# PWR_MGMT.net
KiCad netlist of a schematic drawn in Altium Designer
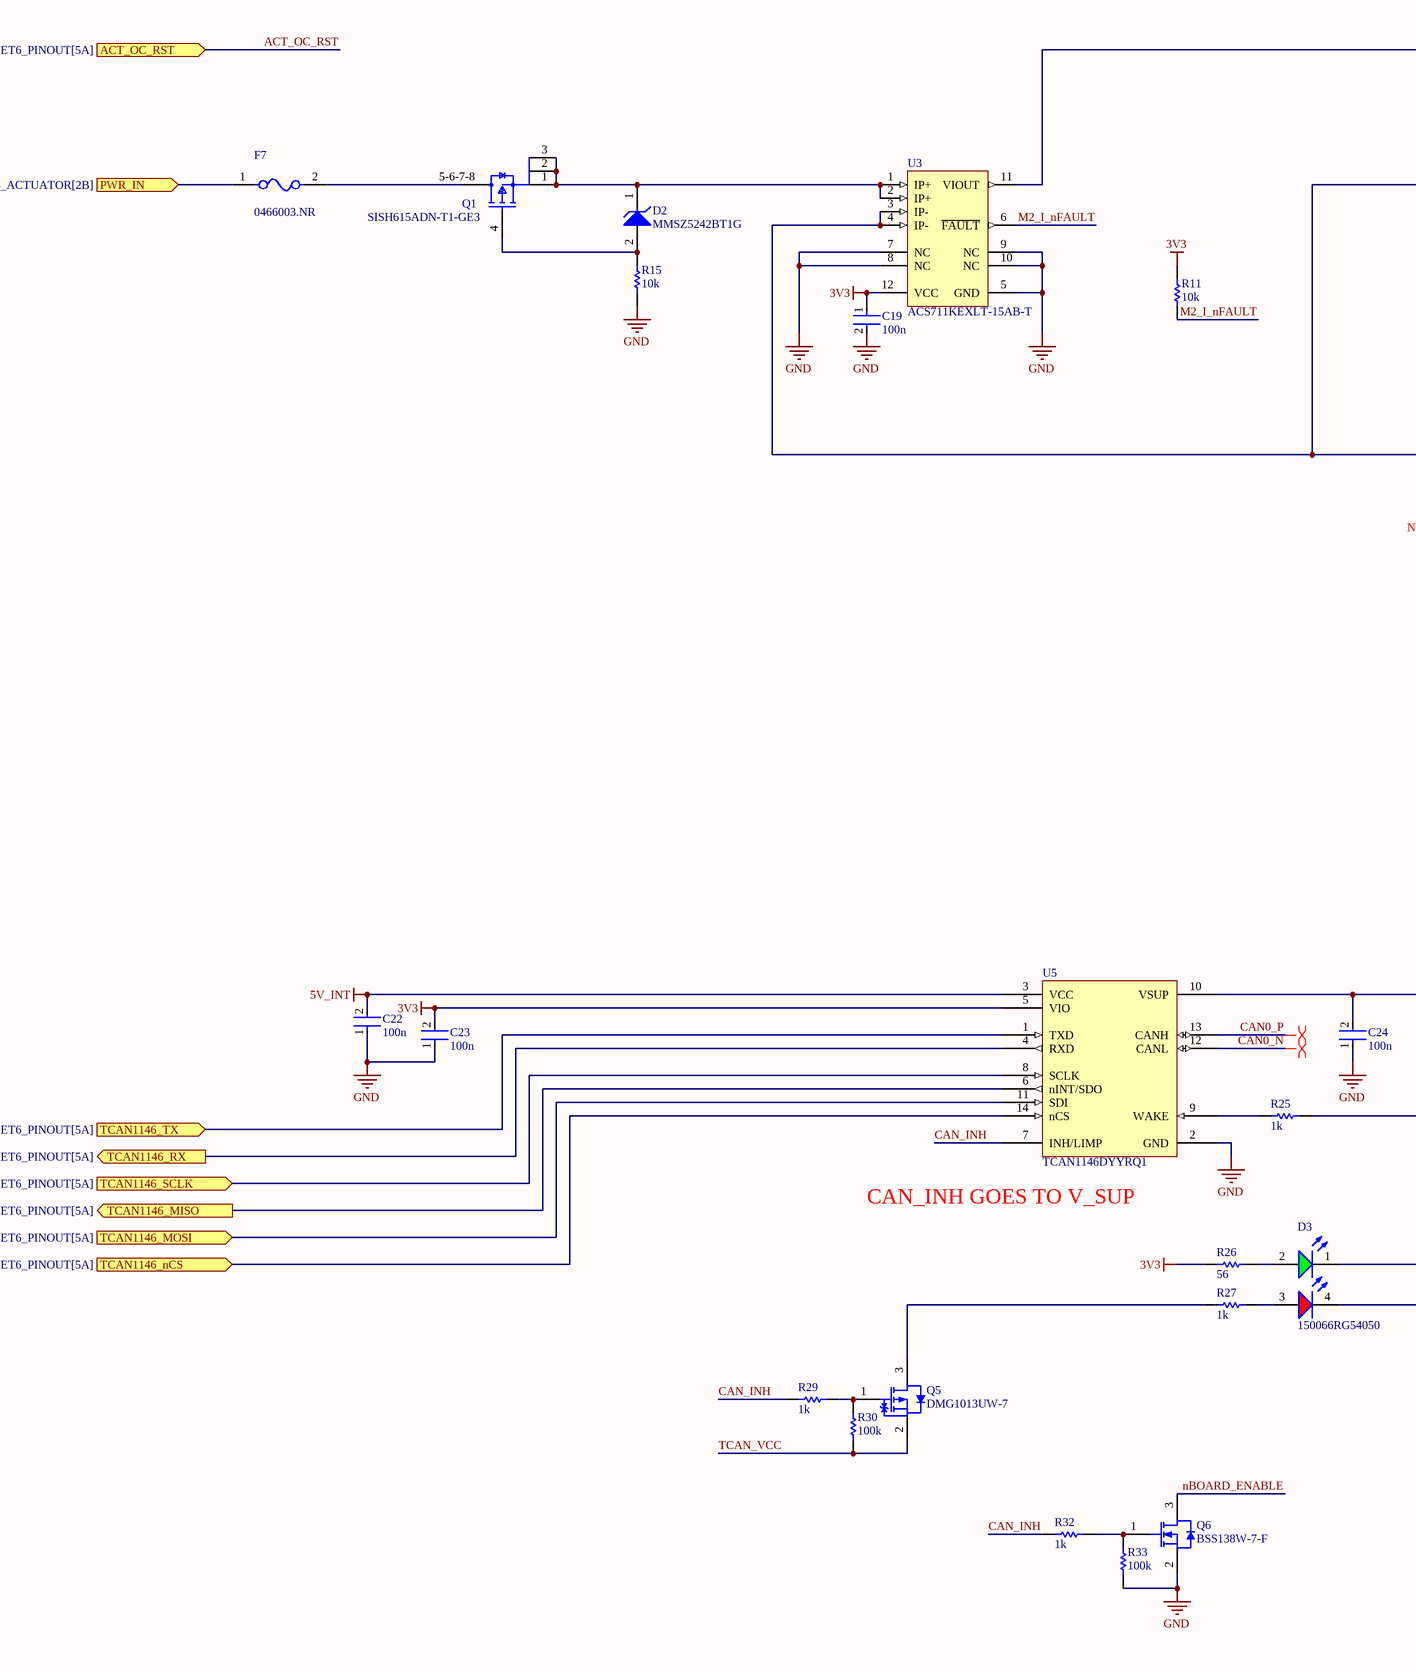
[diagram p0: PWR_MGMT.SchDoc, left]
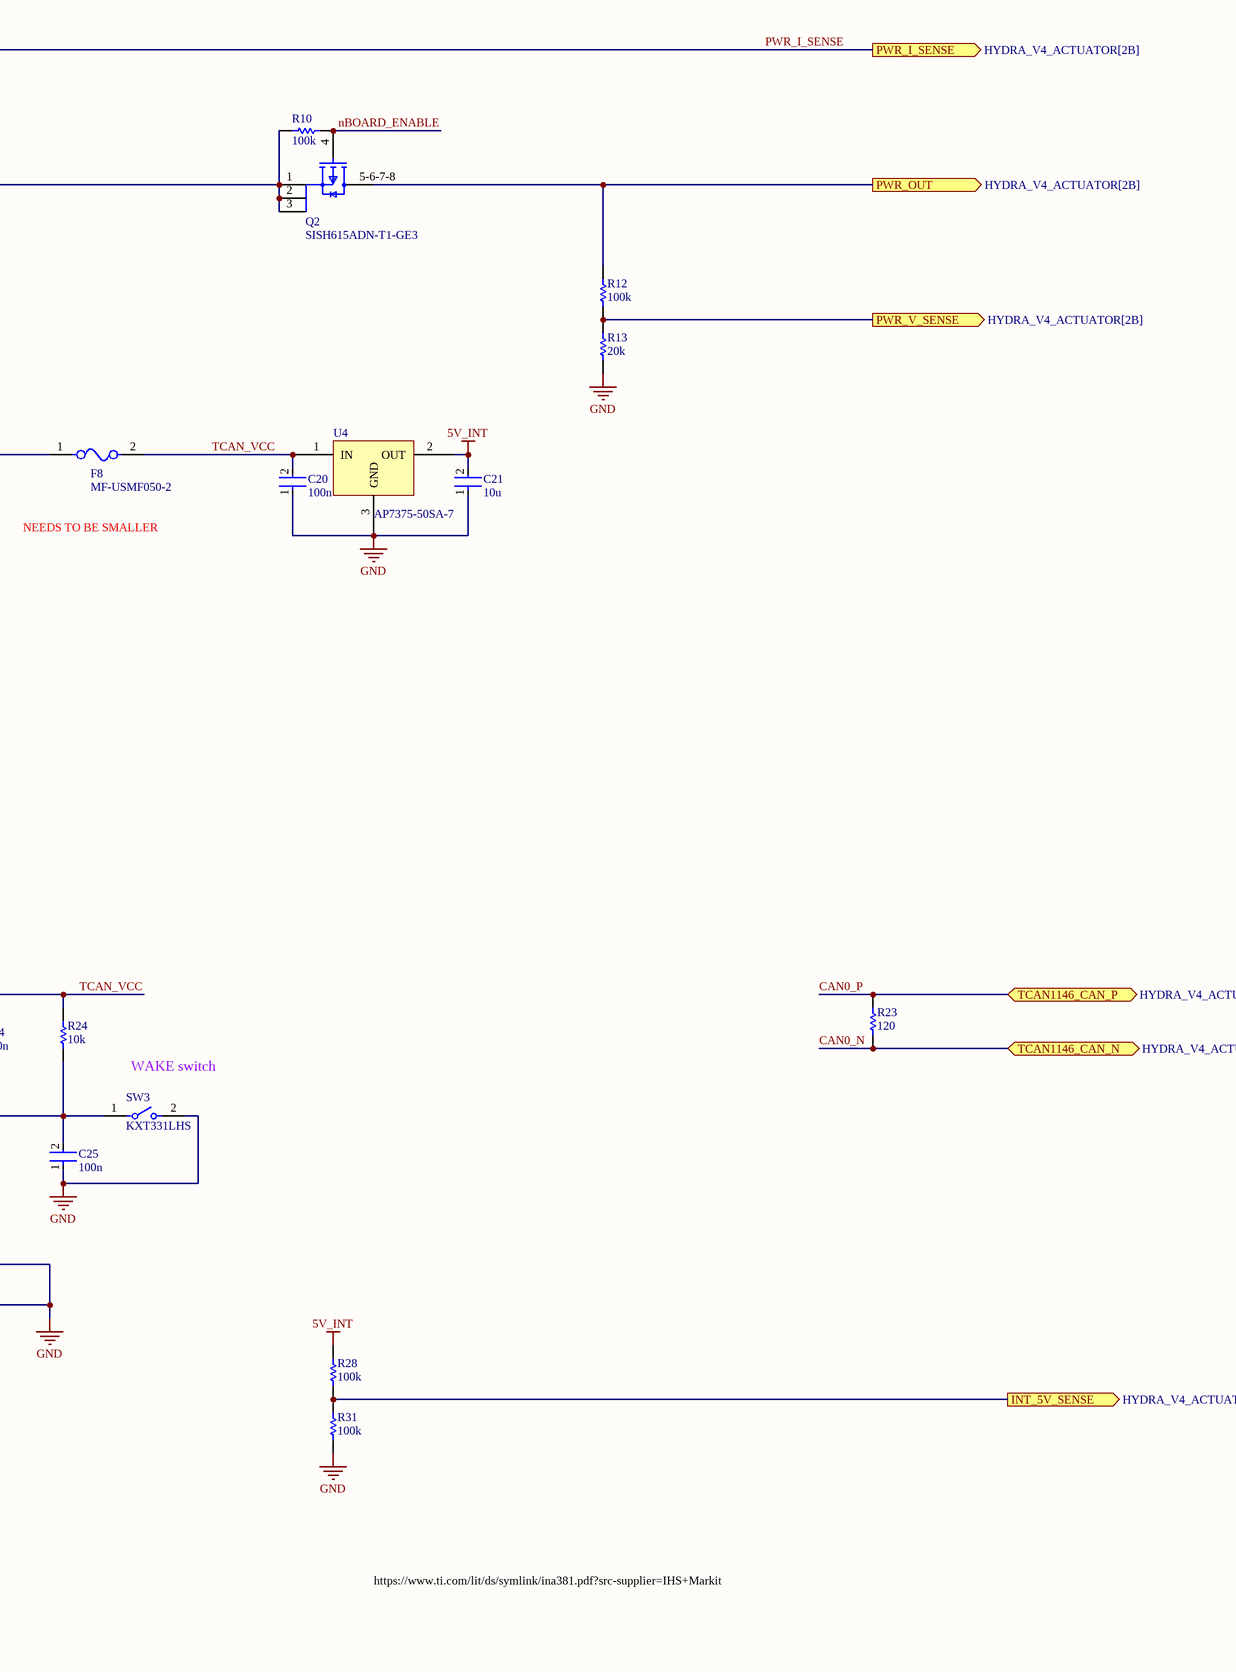
[diagram p1: PWR_MGMT.SchDoc, right]

(export (version "E")
  (design (tool "Eeschema 10.0.6"))
  (components
    (comp (ref "C19")
      (value "100n")
      (footprint "FP-0402-L_1_0_0_05-W_0_5-IPC_A")
      (description "LARGE PADS, 0402 CAP, CHANGE COMMENT TO MATCH REAL P/N")
      (libsource (lib "Space Concordia") (part "b4654b650e69147ec39a6b967a45e02"))
    )
    (comp (ref "C20")
      (value "100n")
      (footprint "FP-0402-L_1_0_0_05-W_0_5-IPC_A")
      (description "LARGE PADS, 0402 CAP, CHANGE COMMENT TO MATCH REAL P/N")
      (libsource (lib "Space Concordia") (part "b4654b650e69147ec39a6b967a45e02"))
    )
    (comp (ref "C21")
      (value "10u")
      (footprint "FP-0402-L_1_0_0_05-W_0_5-IPC_A")
      (description "LARGE PADS, 0402 CAP, CHANGE COMMENT TO MATCH REAL P/N")
      (libsource (lib "Space Concordia") (part "b4654b650e69147ec39a6b967a45e02"))
    )
    (comp (ref "C22")
      (value "100n")
      (footprint "FP-0402-L_1_0_0_05-W_0_5-IPC_A")
      (description "LARGE PADS, 0402 CAP, CHANGE COMMENT TO MATCH REAL P/N")
      (libsource (lib "Space Concordia") (part "b4654b650e69147ec39a6b967a45e02"))
    )
    (comp (ref "C23")
      (value "100n")
      (footprint "FP-0402-L_1_0_0_05-W_0_5-IPC_A")
      (description "LARGE PADS, 0402 CAP, CHANGE COMMENT TO MATCH REAL P/N")
      (libsource (lib "Space Concordia") (part "b4654b650e69147ec39a6b967a45e02"))
    )
    (comp (ref "C24")
      (value "100n")
      (footprint "FP-0402-L_1_0_0_05-W_0_5-IPC_A")
      (description "LARGE PADS, 0402 CAP, CHANGE COMMENT TO MATCH REAL P/N")
      (libsource (lib "Space Concordia") (part "b4654b650e69147ec39a6b967a45e02"))
    )
    (comp (ref "C25")
      (value "100n")
      (footprint "FP-0402-L_1_0_0_05-W_0_5-IPC_A")
      (description "LARGE PADS, 0402 CAP, CHANGE COMMENT TO MATCH REAL P/N")
      (libsource (lib "Space Concordia") (part "b4654b650e69147ec39a6b967a45e02"))
    )
    (comp (ref "D2")
      (value "MMSZ5242BT1G")
      (footprint "ONSC-SOD-123-2-425-04_V")
      (description "Zener Voltage Regulator, 500 mW, 2-Pin SOD-123, Pb-Free, Tape and Reel")
      (fields (field (name "MANUFACTURER") "On Semiconductor"))
      (libsource (lib "Altium Content Vault") (part "ONSC-K1A2-2"))
    )
    (comp (ref "D3")
      (value "150066RG54050")
      (footprint "WL-SBCD_0606")
      (description "Led, Red/Grn, 180Mcd/230Mcd, 624Nm/525Nm Rohs Compliant: Yes")
      (fields (field (name "SOURCE") "rgled.SchLib"))
      (libsource (lib "Space Concordia") (part "CMP-004-00034-2"))
    )
    (comp (ref "F7")
      (value "0466003.NR")
      (footprint "FP-0466-MFG")
      (description "FUSE BOARD MNT 3A 32VAC/VDC 1206")
      (fields
        (field (name "OCTOPART") "https://octopart.com/0466003.nr-littelfuse-565175")
        (field (name "MANUFACTURER") "Littelfuse")
      )
      (libsource (lib "Altium Content Vault") (part "5bcf9b9f640e542cf0359d10258e979"))
    )
    (comp (ref "F8")
      (value "MF-USMF050-2")
      (footprint "FP-MF-USMF-MFG")
      (description "PTC RESET FUSE 13.2V 500MA 1210")
      (fields
        (field (name "MANUFACTURER") "Bourns Inc.")
        (field (name "OCTOPART") "https://octopart.com/mf-usmf050-2-bourns-97645")
      )
      (libsource (lib "Altium Content Vault") (part "5bcf9b9f640e542cf0359d10258e979"))
    )
    (comp (ref "Q1")
      (value "SISH615ADN-T1-GE3")
      (footprint "SISH615ADN-T1-GE3-Footprint-1")
      (description "Trans MOSFET P-CH 20V 22.1A 8-Pin PowerPAK 1212 EP T/R")
      (libsource (lib "Space Concordia") (part "CMP-013-00036-4"))
    )
    (comp (ref "Q2")
      (value "SISH615ADN-T1-GE3")
      (footprint "SISH615ADN-T1-GE3-Footprint-1")
      (description "Trans MOSFET P-CH 20V 22.1A 8-Pin PowerPAK 1212 EP T/R")
      (libsource (lib "Space Concordia") (part "CMP-013-00036-4"))
    )
    (comp (ref "Q5")
      (value "DMG1013UW-7")
      (footprint "DIOD-SOT323-3_V")
      (fields (field (name "MANUFACTURER") "Diodes Inc"))
      (libsource (lib "Altium Content Vault") (part "PEMOS-GSD-3_C"))
    )
    (comp (ref "Q6")
      (value "BSS138W-7-F")
      (footprint "DIOD-SOT323-3_V")
      (fields (field (name "MANUFACTURER") "DiodesIncorporated"))
      (libsource (lib "Altium Content Vault") (part "NEMOS-GSD-3"))
    )
    (comp (ref "R10")
      (value "100k")
      (footprint "R0603B")
      (description "Resistor")
      (libsource (lib "Space Concordia") (part "Resistor"))
    )
    (comp (ref "R11")
      (value "10k")
      (footprint "R0603B")
      (description "Resistor")
      (libsource (lib "Space Concordia") (part "Resistor"))
    )
    (comp (ref "R12")
      (value "100k")
      (footprint "R0603B")
      (description "Resistor")
      (libsource (lib "Space Concordia") (part "Resistor"))
    )
    (comp (ref "R13")
      (value "20k")
      (footprint "R0603B")
      (description "Resistor")
      (libsource (lib "Space Concordia") (part "Resistor"))
    )
    (comp (ref "R15")
      (value "10k")
      (footprint "R0603B")
      (description "Resistor")
      (libsource (lib "Space Concordia") (part "Resistor"))
    )
    (comp (ref "R23")
      (value "120")
      (footprint "R0603B")
      (description "Resistor")
      (libsource (lib "Space Concordia") (part "Resistor"))
    )
    (comp (ref "R24")
      (value "10k")
      (footprint "R0603B")
      (description "Resistor")
      (libsource (lib "Space Concordia") (part "Resistor"))
    )
    (comp (ref "R25")
      (value "1k")
      (footprint "R0603B")
      (description "Resistor")
      (libsource (lib "Space Concordia") (part "Resistor"))
    )
    (comp (ref "R26")
      (value "56")
      (footprint "R0603B")
      (description "Resistor")
      (libsource (lib "Space Concordia") (part "Resistor"))
    )
    (comp (ref "R27")
      (value "1k")
      (footprint "R0603B")
      (description "Resistor")
      (libsource (lib "Space Concordia") (part "Resistor"))
    )
    (comp (ref "R28")
      (value "100k")
      (footprint "R0603B")
      (description "Resistor")
      (libsource (lib "Space Concordia") (part "Resistor"))
    )
    (comp (ref "R29")
      (value "1k")
      (footprint "R0603B")
      (description "Resistor")
      (libsource (lib "Space Concordia") (part "Resistor"))
    )
    (comp (ref "R30")
      (value "100k")
      (footprint "R0603B")
      (description "Resistor")
      (libsource (lib "Space Concordia") (part "Resistor"))
    )
    (comp (ref "R31")
      (value "100k")
      (footprint "R0603B")
      (description "Resistor")
      (libsource (lib "Space Concordia") (part "Resistor"))
    )
    (comp (ref "R32")
      (value "1k")
      (footprint "R0603B")
      (description "Resistor")
      (libsource (lib "Space Concordia") (part "Resistor"))
    )
    (comp (ref "R33")
      (value "100k")
      (footprint "R0603B")
      (description "Resistor")
      (libsource (lib "Space Concordia") (part "Resistor"))
    )
    (comp (ref "SW3")
      (value "KXT331LHS")
      (footprint "FP-KXT331LHS-MFG")
      (description "SWITCH TACTILE SPST-NO 0.02A 15V")
      (libsource (lib "Altium Content Vault") (part "bb27bde45df87f1f469753f287ef5ae"))
    )
    (comp (ref "U3")
      (value "ACS711KEXLT-15AB-T")
      (footprint "ALEG-EX-12_V")
      (libsource (lib "Altium Content Vault") (part "ALEG-ACS711-QFN-12"))
    )
    (comp (ref "U4")
      (value "AP7375-50SA-7")
      (footprint "AP7375-50SA-7-Footprint-1")
      (description "Ldo Cmos Lowcurr SOT23 T&r 3K")
      (libsource (lib "Space Concordia") (part "AP7375-50SA-7"))
    )
    (comp (ref "U5")
      (value "TCAN1146DYYRQ1")
      (footprint "TCAN1146DYYRQ1-Footprint-1")
      (libsource (lib "Space Concordia") (part "CMP-015-00012-2"))
    )
  )
  (nets
    (net (code "2") (name "/CAN0_N") (class "Default")
      (node (ref "R23") (pin "1") (pinfunction "1_1") (pintype "passive"))
      (node (ref "U5") (pin "12") (pinfunction "CANL_12") (pintype "bidirectional"))
    )
    (net (code "3") (name "/CAN0_P") (class "Default")
      (node (ref "R23") (pin "2") (pinfunction "2_2") (pintype "passive"))
      (node (ref "U5") (pin "13") (pinfunction "CANH_13") (pintype "bidirectional"))
    )
    (net (code "4") (name "/CAN_INH") (class "Default")
      (node (ref "R29") (pin "2") (pinfunction "2_2") (pintype "passive"))
      (node (ref "R32") (pin "2") (pinfunction "2_2") (pintype "passive"))
      (node (ref "U5") (pin "7") (pinfunction "INH/LIMP_7") (pintype "passive"))
    )
    (net (code "5") (name "/INT_5V_SENSE") (class "Default")
      (node (ref "R28") (pin "1") (pinfunction "1_1") (pintype "passive"))
      (node (ref "R31") (pin "2") (pinfunction "2_2") (pintype "passive"))
    )
    (net (code "6") (name "/M2_I_nFAULT") (class "Default")
      (node (ref "R11") (pin "1") (pinfunction "1_1") (pintype "passive"))
      (node (ref "U3") (pin "6") (pinfunction "~{FAULT}_6") (pintype "output"))
    )
    (net (code "7") (name "/PWR_IN") (class "Default")
      (node (ref "F7") (pin "1") (pinfunction "1_1") (pintype "passive"))
    )
    (net (code "8") (name "/PWR_I_SENSE") (class "Default")
      (node (ref "U3") (pin "11") (pinfunction "VIOUT_11") (pintype "output"))
    )
    (net (code "9") (name "/PWR_OUT") (class "Default")
      (node (ref "Q2") (pin "5-6-7-8") (pinfunction "D_5-6-7-8") (pintype "passive"))
      (node (ref "R12") (pin "2") (pinfunction "2_2") (pintype "passive"))
    )
    (net (code "10") (name "/PWR_V_SENSE") (class "Default")
      (node (ref "R12") (pin "1") (pinfunction "1_1") (pintype "passive"))
      (node (ref "R13") (pin "2") (pinfunction "2_2") (pintype "passive"))
    )
    (net (code "11") (name "/TCAN1146_MISO") (class "Default")
      (node (ref "U5") (pin "6") (pinfunction "nINT/SDO_6") (pintype "output"))
    )
    (net (code "12") (name "/TCAN1146_MOSI") (class "Default")
      (node (ref "U5") (pin "11") (pinfunction "SDI_11") (pintype "input"))
    )
    (net (code "13") (name "/TCAN1146_RX") (class "Default")
      (node (ref "U5") (pin "4") (pinfunction "RXD_4") (pintype "output"))
    )
    (net (code "14") (name "/TCAN1146_SCLK") (class "Default")
      (node (ref "U5") (pin "8") (pinfunction "SCLK_8") (pintype "input"))
    )
    (net (code "15") (name "/TCAN1146_TX") (class "Default")
      (node (ref "U5") (pin "1") (pinfunction "TXD_1") (pintype "input"))
    )
    (net (code "16") (name "/TCAN1146_nCS") (class "Default")
      (node (ref "U5") (pin "14") (pinfunction "nCS_14") (pintype "input"))
    )
    (net (code "17") (name "/TCAN_VCC") (class "Default")
      (node (ref "C20") (pin "2") (pinfunction "2_2") (pintype "passive"))
      (node (ref "C24") (pin "2") (pinfunction "2_2") (pintype "passive"))
      (node (ref "F8") (pin "2") (pinfunction "2_2") (pintype "passive"))
      (node (ref "Q5") (pin "2") (pinfunction "S_2") (pintype "passive"))
      (node (ref "R24") (pin "2") (pinfunction "2_2") (pintype "passive"))
      (node (ref "R30") (pin "2") (pinfunction "2_2") (pintype "passive"))
      (node (ref "U4") (pin "1") (pinfunction "IN_1") (pintype "passive"))
      (node (ref "U5") (pin "10") (pinfunction "VSUP_10") (pintype "power_in"))
    )
    (net (code "18") (name "/nBOARD_ENABLE") (class "Default")
      (node (ref "Q2") (pin "4") (pinfunction "G_4") (pintype "passive"))
      (node (ref "Q6") (pin "3") (pinfunction "D_3") (pintype "passive"))
      (node (ref "R10") (pin "2") (pinfunction "2_2") (pintype "passive"))
    )
    (net (code "19") (name "3V3") (class "Default")
      (node (ref "C19") (pin "1") (pinfunction "1_1") (pintype "passive"))
      (node (ref "C23") (pin "2") (pinfunction "2_2") (pintype "passive"))
      (node (ref "R11") (pin "2") (pinfunction "2_2") (pintype "passive"))
      (node (ref "R26") (pin "2") (pinfunction "2_2") (pintype "passive"))
      (node (ref "U3") (pin "12") (pinfunction "VCC_12") (pintype "power_in"))
      (node (ref "U5") (pin "5") (pinfunction "VIO_5") (pintype "power_in"))
    )
    (net (code "20") (name "5V_INT") (class "Default")
      (node (ref "C21") (pin "2") (pinfunction "2_2") (pintype "passive"))
      (node (ref "C22") (pin "2") (pinfunction "2_2") (pintype "passive"))
      (node (ref "R28") (pin "2") (pinfunction "2_2") (pintype "passive"))
      (node (ref "U4") (pin "2") (pinfunction "OUT_2") (pintype "passive"))
      (node (ref "U5") (pin "3") (pinfunction "VCC_3") (pintype "power_in"))
    )
    (net (code "21") (name "GND") (class "Default")
      (node (ref "C19") (pin "2") (pinfunction "2_2") (pintype "passive"))
      (node (ref "C20") (pin "1") (pinfunction "1_1") (pintype "passive"))
      (node (ref "C21") (pin "1") (pinfunction "1_1") (pintype "passive"))
      (node (ref "C22") (pin "1") (pinfunction "1_1") (pintype "passive"))
      (node (ref "C23") (pin "1") (pinfunction "1_1") (pintype "passive"))
      (node (ref "C24") (pin "1") (pinfunction "1_1") (pintype "passive"))
      (node (ref "C25") (pin "1") (pinfunction "1_1") (pintype "passive"))
      (node (ref "D3") (pin "1") (pinfunction "K_1") (pintype "passive"))
      (node (ref "D3") (pin "4") (pinfunction "K_4") (pintype "passive"))
      (node (ref "Q6") (pin "2") (pinfunction "S_2") (pintype "passive"))
      (node (ref "R13") (pin "1") (pinfunction "1_1") (pintype "passive"))
      (node (ref "R15") (pin "1") (pinfunction "1_1") (pintype "passive"))
      (node (ref "R31") (pin "1") (pinfunction "1_1") (pintype "passive"))
      (node (ref "R33") (pin "1") (pinfunction "1_1") (pintype "passive"))
      (node (ref "SW3") (pin "2") (pinfunction "2_2") (pintype "passive"))
      (node (ref "U3") (pin "10") (pinfunction "NC_10") (pintype "passive"))
      (node (ref "U3") (pin "5") (pinfunction "GND_5") (pintype "power_in"))
      (node (ref "U3") (pin "7") (pinfunction "NC_7") (pintype "passive"))
      (node (ref "U3") (pin "8") (pinfunction "NC_8") (pintype "passive"))
      (node (ref "U3") (pin "9") (pinfunction "NC_9") (pintype "passive"))
      (node (ref "U4") (pin "3") (pinfunction "GND_3") (pintype "passive"))
      (node (ref "U5") (pin "2") (pinfunction "GND_2") (pintype "power_in"))
    )
    (net (code "22") (name "Net-(C25-Pad2)") (class "Default")
      (node (ref "C25") (pin "2") (pinfunction "2_2") (pintype "passive"))
      (node (ref "R24") (pin "1") (pinfunction "1_1") (pintype "passive"))
      (node (ref "R25") (pin "1") (pinfunction "1_1") (pintype "passive"))
      (node (ref "SW3") (pin "1") (pinfunction "1_1") (pintype "passive"))
    )
    (net (code "23") (name "Net-(D2-A)") (class "Default")
      (node (ref "D2") (pin "2") (pinfunction "A_2") (pintype "passive"))
      (node (ref "Q1") (pin "4") (pinfunction "G_4") (pintype "passive"))
      (node (ref "R15") (pin "2") (pinfunction "2_2") (pintype "passive"))
    )
    (net (code "24") (name "Net-(D2-K)") (class "Default")
      (node (ref "D2") (pin "1") (pinfunction "K_1") (pintype "passive"))
      (node (ref "Q1") (pin "1") (pinfunction "S_1") (pintype "passive"))
      (node (ref "Q1") (pin "2") (pinfunction "S_2") (pintype "passive"))
      (node (ref "Q1") (pin "3") (pinfunction "S_3") (pintype "passive"))
      (node (ref "U3") (pin "1") (pinfunction "IP+_1") (pintype "input"))
      (node (ref "U3") (pin "2") (pinfunction "IP+_2") (pintype "input"))
    )
    (net (code "25") (name "Net-(D3-A-Pad2)") (class "Default")
      (node (ref "D3") (pin "2") (pinfunction "A_2") (pintype "passive"))
      (node (ref "R26") (pin "1") (pinfunction "1_1") (pintype "passive"))
    )
    (net (code "26") (name "Net-(D3-A-Pad3)") (class "Default")
      (node (ref "D3") (pin "3") (pinfunction "A_3") (pintype "passive"))
      (node (ref "R27") (pin "1") (pinfunction "1_1") (pintype "passive"))
    )
    (net (code "27") (name "Net-(F8-Pad1)") (class "Default")
      (node (ref "F8") (pin "1") (pinfunction "1_1") (pintype "passive"))
      (node (ref "Q2") (pin "1") (pinfunction "S_1") (pintype "passive"))
      (node (ref "Q2") (pin "2") (pinfunction "S_2") (pintype "passive"))
      (node (ref "Q2") (pin "3") (pinfunction "S_3") (pintype "passive"))
      (node (ref "R10") (pin "1") (pinfunction "1_1") (pintype "passive"))
      (node (ref "U3") (pin "3") (pinfunction "IP-_3") (pintype "input"))
      (node (ref "U3") (pin "4") (pinfunction "IP-_4") (pintype "input"))
    )
    (net (code "28") (name "Net-(Q1-D)") (class "Default")
      (node (ref "F7") (pin "2") (pinfunction "2_2") (pintype "passive"))
      (node (ref "Q1") (pin "5-6-7-8") (pinfunction "D_5-6-7-8") (pintype "passive"))
    )
    (net (code "29") (name "Net-(Q5-D)") (class "Default")
      (node (ref "Q5") (pin "3") (pinfunction "D_3") (pintype "passive"))
      (node (ref "R27") (pin "2") (pinfunction "2_2") (pintype "passive"))
    )
    (net (code "30") (name "Net-(Q5-G)") (class "Default")
      (node (ref "Q5") (pin "1") (pinfunction "G_1") (pintype "passive"))
      (node (ref "R29") (pin "1") (pinfunction "1_1") (pintype "passive"))
      (node (ref "R30") (pin "1") (pinfunction "1_1") (pintype "passive"))
    )
    (net (code "31") (name "Net-(Q6-G)") (class "Default")
      (node (ref "Q6") (pin "1") (pinfunction "G_1") (pintype "passive"))
      (node (ref "R32") (pin "1") (pinfunction "1_1") (pintype "passive"))
      (node (ref "R33") (pin "2") (pinfunction "2_2") (pintype "passive"))
    )
    (net (code "32") (name "Net-(U5-WAKE)") (class "Default")
      (node (ref "R25") (pin "2") (pinfunction "2_2") (pintype "passive"))
      (node (ref "U5") (pin "9") (pinfunction "WAKE_9") (pintype "input"))
    )
  )
)
